# Source.net
KiCad netlist of a schematic drawn in Altium Designer
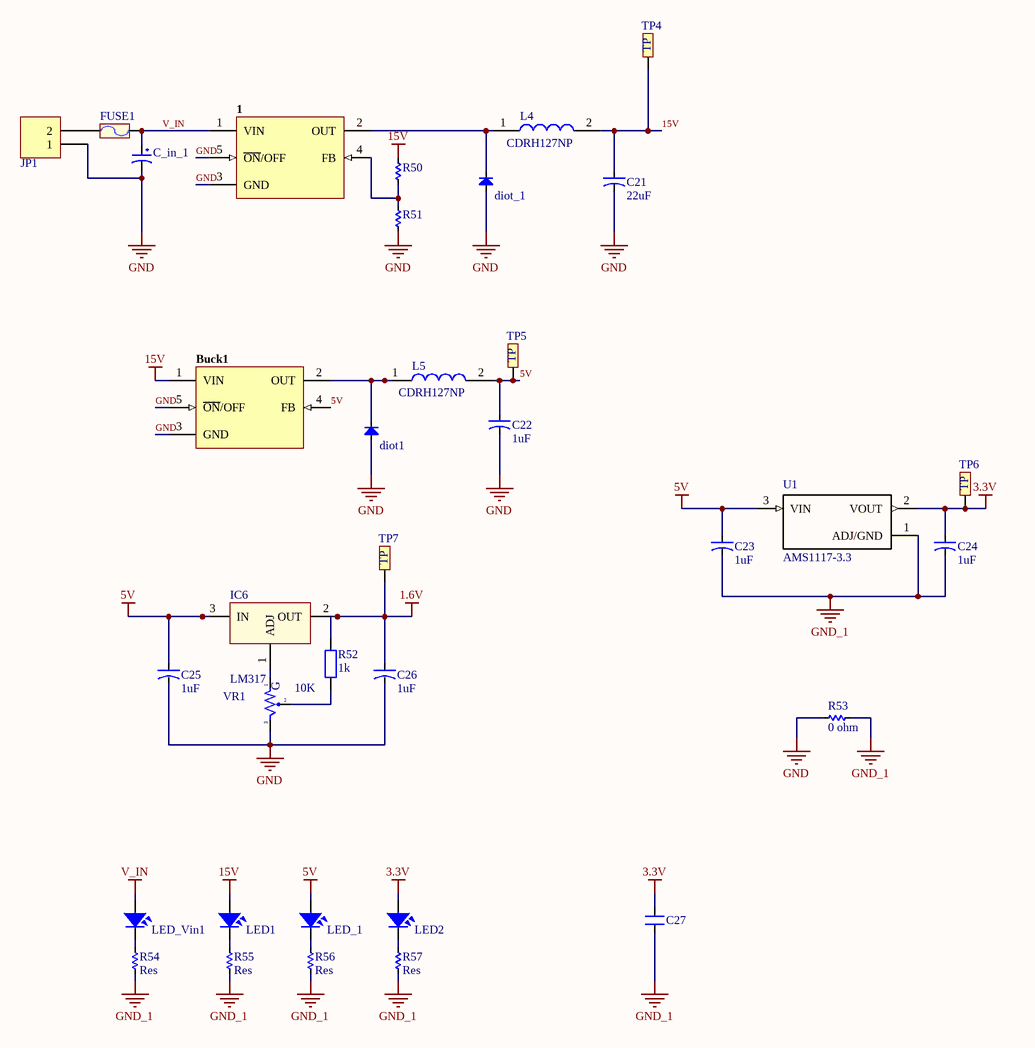
[diagram p0: Source.SchDoc]

(export (version "E")
  (design (tool "Eeschema 10.0.6"))
  (components
    (comp (ref "1") (value "LM2576") (footprint "TO263") (libsource (lib "LIBRARY") (part "LM2576")))
    (comp (ref "Buck1") (value "LM2576") (footprint "TO263") (libsource (lib "LIBRARY") (part "LM2576")))
    (comp (ref "C21")
      (value "22uF")
      (footprint "CA-ALU-2.54")
      (description "Capacitor (Semiconductor SIM Model)")
      (fields (field (name "PUBLISHER") "Altium Limited"))
      (libsource (lib "LIBRARY") (part "CN-ALU-DIP"))
    )
    (comp (ref "C22")
      (value "1uF")
      (footprint "CA-ALU-2.54")
      (description "Capacitor (Semiconductor SIM Model)")
      (fields (field (name "PUBLISHER") "Altium Limited"))
      (libsource (lib "LIBRARY") (part "CN-ALU-DIP"))
    )
    (comp (ref "C23")
      (value "1uF")
      (footprint "CA-ALU-2.54")
      (description "Capacitor (Semiconductor SIM Model)")
      (fields (field (name "PUBLISHER") "Altium Limited"))
      (libsource (lib "LIBRARY") (part "CN-ALU-DIP"))
    )
    (comp (ref "C24")
      (value "1uF")
      (footprint "CA-ALU-2.54")
      (description "Capacitor (Semiconductor SIM Model)")
      (fields (field (name "PUBLISHER") "Altium Limited"))
      (libsource (lib "LIBRARY") (part "CN-ALU-DIP"))
    )
    (comp (ref "C25")
      (value "1uF")
      (footprint "CA-ALU-2.54")
      (description "Capacitor (Semiconductor SIM Model)")
      (fields (field (name "PUBLISHER") "Altium Limited"))
      (libsource (lib "LIBRARY") (part "CN-ALU-DIP"))
    )
    (comp (ref "C26")
      (value "1uF")
      (footprint "CA-ALU-2.54")
      (description "Capacitor (Semiconductor SIM Model)")
      (fields (field (name "PUBLISHER") "Altium Limited"))
      (libsource (lib "LIBRARY") (part "CN-ALU-DIP"))
    )
    (comp (ref "C27") (value "104,0805") (footprint "CN-SMD-0805") (libsource (lib "LIBRARY") (part "CN")))
    (comp (ref "C_in_1")
      (value "100uF")
      (footprint "CP1.5/3.4")
      (description "Cap 1000uF/16V - 220uF/50V")
      (libsource (lib "syhaunguyen") (part "CP4"))
    )
    (comp (ref "diot1")
      (value "Diode SMD")
      (footprint "DIO-SMD-106")
      (description "Default Diode")
      (fields (field (name "PUBLISHER") "Altium Limited"))
      (libsource (lib "LIBRARY") (part "Diode SMD"))
    )
    (comp (ref "diot_1")
      (value "Diode SMD")
      (footprint "DIO-SMD-106")
      (description "Default Diode")
      (fields (field (name "PUBLISHER") "Altium Limited"))
      (libsource (lib "LIBRARY") (part "Diode SMD"))
    )
    (comp (ref "FUSE1")
      (value "F1A")
      (footprint "Fuse1")
      (description "Fuse")
      (fields (field (name "DESIGNED BY") "VanDungEvn"))
      (libsource (lib "LIBRARY") (part "Fuse"))
    )
    (comp (ref "IC6")
      (value "LM317")
      (footprint "TO220NH")
      (description "Adj Voltage +1.2 -> +37V")
      (libsource (lib "LIBRARY") (part "LM317"))
    )
    (comp (ref "JP1")
      (value "Header 2_1")
      (footprint "HED2")
      (description "Header, 2-Pin")
      (fields (field (name "MANUFACTURER") "Generic Components"))
      (libsource (lib "syhaunguyen") (part "Header 2_1"))
    )
    (comp (ref "L4")
      (value "CDRH127NP")
      (footprint "INDPM120120X800N")
      (description "Inductor")
      (fields
        (field (name "MANUFACTURER_PART_NUMBER") "CDRH127NP-330MC")
        (field (name "MOUSER PART NUMBER") "851-CDRH127NP-330MC")
      )
      (libsource (lib "SemacSYS") (part "CDRH127NP-330MC"))
    )
    (comp (ref "L5")
      (value "CDRH127NP")
      (footprint "INDPM120120X800N")
      (description "Inductor")
      (fields
        (field (name "MANUFACTURER_PART_NUMBER") "CDRH127NP-330MC")
        (field (name "MOUSER PART NUMBER") "851-CDRH127NP-330MC")
      )
      (libsource (lib "SemacSYS") (part "CDRH127NP-330MC"))
    )
    (comp (ref "LED1")
      (value "power 0805")
      (footprint "LED-0805-Blue")
      (libsource (lib "LIBRARY") (part "LED SMD"))
    )
    (comp (ref "LED2")
      (value "power 0805")
      (footprint "LED-0805-Blue")
      (libsource (lib "LIBRARY") (part "LED SMD"))
    )
    (comp (ref "LED_1")
      (value "power 0805")
      (footprint "LED-0805-Blue")
      (libsource (lib "LIBRARY") (part "LED SMD"))
    )
    (comp (ref "LED_Vin1")
      (value "power 0805")
      (footprint "LED-0805-Blue")
      (libsource (lib "LIBRARY") (part "LED SMD"))
    )
    (comp (ref "R50")
      (value "Res")
      (footprint "RES-SMD-0805")
      (description "Resistor")
      (fields
        (field (name "MANUFACTURER") "Generic Components")
        (field (name "PUBLISHER") "Altium Hobart Technology Centre")
      )
      (libsource (lib "LIBRARY") (part "Res-SMD"))
    )
    (comp (ref "R51")
      (value "Res")
      (footprint "RES-SMD-0805")
      (description "Resistor")
      (fields
        (field (name "MANUFACTURER") "Generic Components")
        (field (name "PUBLISHER") "Altium Hobart Technology Centre")
      )
      (libsource (lib "LIBRARY") (part "Res-SMD"))
    )
    (comp (ref "R52")
      (value "1k")
      (footprint "R1/4W")
      (description "Resistor 1/4W")
      (libsource (lib "syhaunguyen") (part "R1/4W"))
    )
    (comp (ref "R53")
      (value "0 ohm")
      (footprint "RES-SMD-1206")
      (description "Resistor")
      (fields
        (field (name "MANUFACTURER") "Generic Components")
        (field (name "PUBLISHER") "Altium Hobart Technology Centre")
      )
      (libsource (lib "LIBRARY") (part "Res-SMD"))
    )
    (comp (ref "R54")
      (value "Res")
      (footprint "RES-1/2W")
      (fields
        (field (name "MANUFACTURER") "Generic Components")
        (field (name "PUBLISHER") "Altium Hobart Technology Centre")
      )
      (libsource (lib "LIBRARY1") (part "Res"))
    )
    (comp (ref "R55")
      (value "Res")
      (footprint "RES-1/2W")
      (fields
        (field (name "MANUFACTURER") "Generic Components")
        (field (name "PUBLISHER") "Altium Hobart Technology Centre")
      )
      (libsource (lib "LIBRARY1") (part "Res"))
    )
    (comp (ref "R56")
      (value "Res")
      (footprint "RES-1/2W")
      (fields
        (field (name "MANUFACTURER") "Generic Components")
        (field (name "PUBLISHER") "Altium Hobart Technology Centre")
      )
      (libsource (lib "LIBRARY1") (part "Res"))
    )
    (comp (ref "R57")
      (value "Res")
      (footprint "RES-1/2W")
      (fields
        (field (name "MANUFACTURER") "Generic Components")
        (field (name "PUBLISHER") "Altium Hobart Technology Centre")
      )
      (libsource (lib "LIBRARY1") (part "Res"))
    )
    (comp (ref "TP4")
      (value "~")
      (footprint "TP")
      (description "CONNECT 1")
      (libsource (lib "syhaunguyen") (part "TP"))
    )
    (comp (ref "TP5")
      (value "~")
      (footprint "TP")
      (description "CONNECT 1")
      (libsource (lib "syhaunguyen") (part "TP"))
    )
    (comp (ref "TP6")
      (value "~")
      (footprint "TP")
      (description "CONNECT 1")
      (libsource (lib "syhaunguyen") (part "TP"))
    )
    (comp (ref "TP7")
      (value "~")
      (footprint "TP")
      (description "CONNECT 1")
      (libsource (lib "syhaunguyen") (part "TP"))
    )
    (comp (ref "U1")
      (value "AMS1117-3.3")
      (footprint "*SOT229P700X180-4N")
      (description "Sot223/Pkg 1-Amp 3.3-Volt Low Drop Out Voltage Regulatator")
      (fields (field (name "MF") "Advanced Monolithic Systems"))
      (libsource (lib "SemacSYS") (part "AMS1117-3.3"))
    )
    (comp (ref "VR1")
      (value "10K")
      (footprint "VR-S2")
      (description "Var Resistor")
      (libsource (lib "LIBRARY1") (part "VR-S"))
    )
  )
  (nets
    (net (code "1") (name "1.6V") (class "Default")
      (node (ref "C26") (pin "1") (pinfunction "1_1") (pintype "passive"))
      (node (ref "IC6") (pin "2") (pinfunction "OUT_2") (pintype "passive"))
      (node (ref "R52") (pin "2") (pinfunction "2_2") (pintype "passive"))
      (node (ref "TP7") (pin "TP1") (pinfunction "0_TP1") (pintype "passive"))
    )
    (net (code "2") (name "3.3V") (class "Default")
      (node (ref "C24") (pin "1") (pinfunction "1_1") (pintype "passive"))
      (node (ref "C27") (pin "2") (pinfunction "2_2") (pintype "passive"))
      (node (ref "LED2") (pin "1") (pinfunction "1_1") (pintype "passive"))
      (node (ref "TP6") (pin "TP1") (pinfunction "0_TP1") (pintype "passive"))
      (node (ref "U1") (pin "2") (pinfunction "VOUT_2") (pintype "output"))
    )
    (net (code "3") (name "5V") (class "Default")
      (node (ref "Buck1") (pin "4") (pinfunction "FB_4") (pintype "input"))
      (node (ref "C22") (pin "1") (pinfunction "1_1") (pintype "passive"))
      (node (ref "C23") (pin "1") (pinfunction "1_1") (pintype "passive"))
      (node (ref "C25") (pin "1") (pinfunction "1_1") (pintype "passive"))
      (node (ref "IC6") (pin "3") (pinfunction "IN_3") (pintype "passive"))
      (node (ref "L5") (pin "2") (pinfunction "2_2") (pintype "passive"))
      (node (ref "LED_1") (pin "1") (pinfunction "1_1") (pintype "passive"))
      (node (ref "TP5") (pin "TP1") (pinfunction "0_TP1") (pintype "passive"))
      (node (ref "U1") (pin "3") (pinfunction "VIN_3") (pintype "input"))
    )
    (net (code "4") (name "15V") (class "Default")
      (node (ref "Buck1") (pin "1") (pinfunction "VIN_1") (pintype "power_in"))
      (node (ref "C21") (pin "1") (pinfunction "1_1") (pintype "passive"))
      (node (ref "L4") (pin "2") (pinfunction "2_2") (pintype "passive"))
      (node (ref "LED1") (pin "1") (pinfunction "1_1") (pintype "passive"))
      (node (ref "R50") (pin "1") (pinfunction "1_1") (pintype "passive"))
      (node (ref "TP4") (pin "TP1") (pinfunction "0_TP1") (pintype "passive"))
    )
    (net (code "5") (name "GND") (class "Default")
      (node (ref "1") (pin "3") (pinfunction "GND_3") (pintype "power_in"))
      (node (ref "1") (pin "5") (pinfunction "~{ON}/OFF_5") (pintype "input"))
      (node (ref "Buck1") (pin "3") (pinfunction "GND_3") (pintype "power_in"))
      (node (ref "Buck1") (pin "5") (pinfunction "~{ON}/OFF_5") (pintype "input"))
      (node (ref "C21") (pin "2") (pinfunction "2_2") (pintype "passive"))
      (node (ref "C22") (pin "2") (pinfunction "2_2") (pintype "passive"))
      (node (ref "C25") (pin "2") (pinfunction "2_2") (pintype "passive"))
      (node (ref "C26") (pin "2") (pinfunction "2_2") (pintype "passive"))
      (node (ref "C_in_1") (pin "2") (pinfunction "2_2") (pintype "passive"))
      (node (ref "JP1") (pin "1") (pinfunction "1_1") (pintype "passive"))
      (node (ref "R51") (pin "2") (pinfunction "2_2") (pintype "passive"))
      (node (ref "R53") (pin "1") (pinfunction "1_1") (pintype "passive"))
      (node (ref "VR1") (pin "3") (pinfunction "3_3") (pintype "passive"))
      (node (ref "diot1") (pin "1") (pinfunction "A_1") (pintype "passive"))
      (node (ref "diot_1") (pin "1") (pinfunction "A_1") (pintype "passive"))
    )
    (net (code "6") (name "GND_1") (class "Default")
      (node (ref "C23") (pin "2") (pinfunction "2_2") (pintype "passive"))
      (node (ref "C24") (pin "2") (pinfunction "2_2") (pintype "passive"))
      (node (ref "C27") (pin "1") (pinfunction "1_1") (pintype "passive"))
      (node (ref "R53") (pin "2") (pinfunction "2_2") (pintype "passive"))
      (node (ref "R54") (pin "2") (pinfunction "2_2") (pintype "passive"))
      (node (ref "R55") (pin "2") (pinfunction "2_2") (pintype "passive"))
      (node (ref "R56") (pin "2") (pinfunction "2_2") (pintype "passive"))
      (node (ref "R57") (pin "2") (pinfunction "2_2") (pintype "passive"))
      (node (ref "U1") (pin "1") (pinfunction "ADJ/GND_1") (pintype "power_in"))
    )
    (net (code "7") (name "Net-(1-FB)") (class "Default")
      (node (ref "1") (pin "4") (pinfunction "FB_4") (pintype "input"))
      (node (ref "R50") (pin "2") (pinfunction "2_2") (pintype "passive"))
      (node (ref "R51") (pin "1") (pinfunction "1_1") (pintype "passive"))
    )
    (net (code "8") (name "Net-(1-OUT)") (class "Default")
      (node (ref "1") (pin "2") (pinfunction "OUT_2") (pintype "power_in"))
      (node (ref "L4") (pin "1") (pinfunction "1_1") (pintype "passive"))
      (node (ref "diot_1") (pin "2") (pinfunction "K_2") (pintype "passive"))
    )
    (net (code "9") (name "Net-(Buck1-OUT)") (class "Default")
      (node (ref "Buck1") (pin "2") (pinfunction "OUT_2") (pintype "power_in"))
      (node (ref "L5") (pin "1") (pinfunction "1_1") (pintype "passive"))
      (node (ref "diot1") (pin "2") (pinfunction "K_2") (pintype "passive"))
    )
    (net (code "10") (name "Net-(FUSE1-Pad1)") (class "Default")
      (node (ref "FUSE1") (pin "1") (pinfunction "1_1") (pintype "passive"))
      (node (ref "JP1") (pin "2") (pinfunction "2_2") (pintype "passive"))
    )
    (net (code "11") (name "Net-(IC6-ADJ)") (class "Default")
      (node (ref "IC6") (pin "1") (pinfunction "ADJ_1") (pintype "passive"))
      (node (ref "VR1") (pin "1") (pinfunction "1_1") (pintype "passive"))
    )
    (net (code "12") (name "Net-(LED1-Pad2)") (class "Default")
      (node (ref "LED1") (pin "2") (pinfunction "2_2") (pintype "passive"))
      (node (ref "R55") (pin "1") (pinfunction "1_1") (pintype "passive"))
    )
    (net (code "13") (name "Net-(LED2-Pad2)") (class "Default")
      (node (ref "LED2") (pin "2") (pinfunction "2_2") (pintype "passive"))
      (node (ref "R57") (pin "1") (pinfunction "1_1") (pintype "passive"))
    )
    (net (code "14") (name "Net-(LED_1-Pad2)") (class "Default")
      (node (ref "LED_1") (pin "2") (pinfunction "2_2") (pintype "passive"))
      (node (ref "R56") (pin "1") (pinfunction "1_1") (pintype "passive"))
    )
    (net (code "15") (name "Net-(LED_Vin1-Pad2)") (class "Default")
      (node (ref "LED_Vin1") (pin "2") (pinfunction "2_2") (pintype "passive"))
      (node (ref "R54") (pin "1") (pinfunction "1_1") (pintype "passive"))
    )
    (net (code "16") (name "Net-(R52-Pad1)") (class "Default")
      (node (ref "R52") (pin "1") (pinfunction "1_1") (pintype "passive"))
      (node (ref "VR1") (pin "2") (pinfunction "2_2") (pintype "passive"))
    )
    (net (code "17") (name "V_IN") (class "Default")
      (node (ref "1") (pin "1") (pinfunction "VIN_1") (pintype "power_in"))
      (node (ref "C_in_1") (pin "1") (pinfunction "1_1") (pintype "passive"))
      (node (ref "FUSE1") (pin "2") (pinfunction "2_2") (pintype "passive"))
      (node (ref "LED_Vin1") (pin "1") (pinfunction "1_1") (pintype "passive"))
    )
  )
)
